# IF_RX.net
KiCad netlist of a schematic drawn in Altium Designer
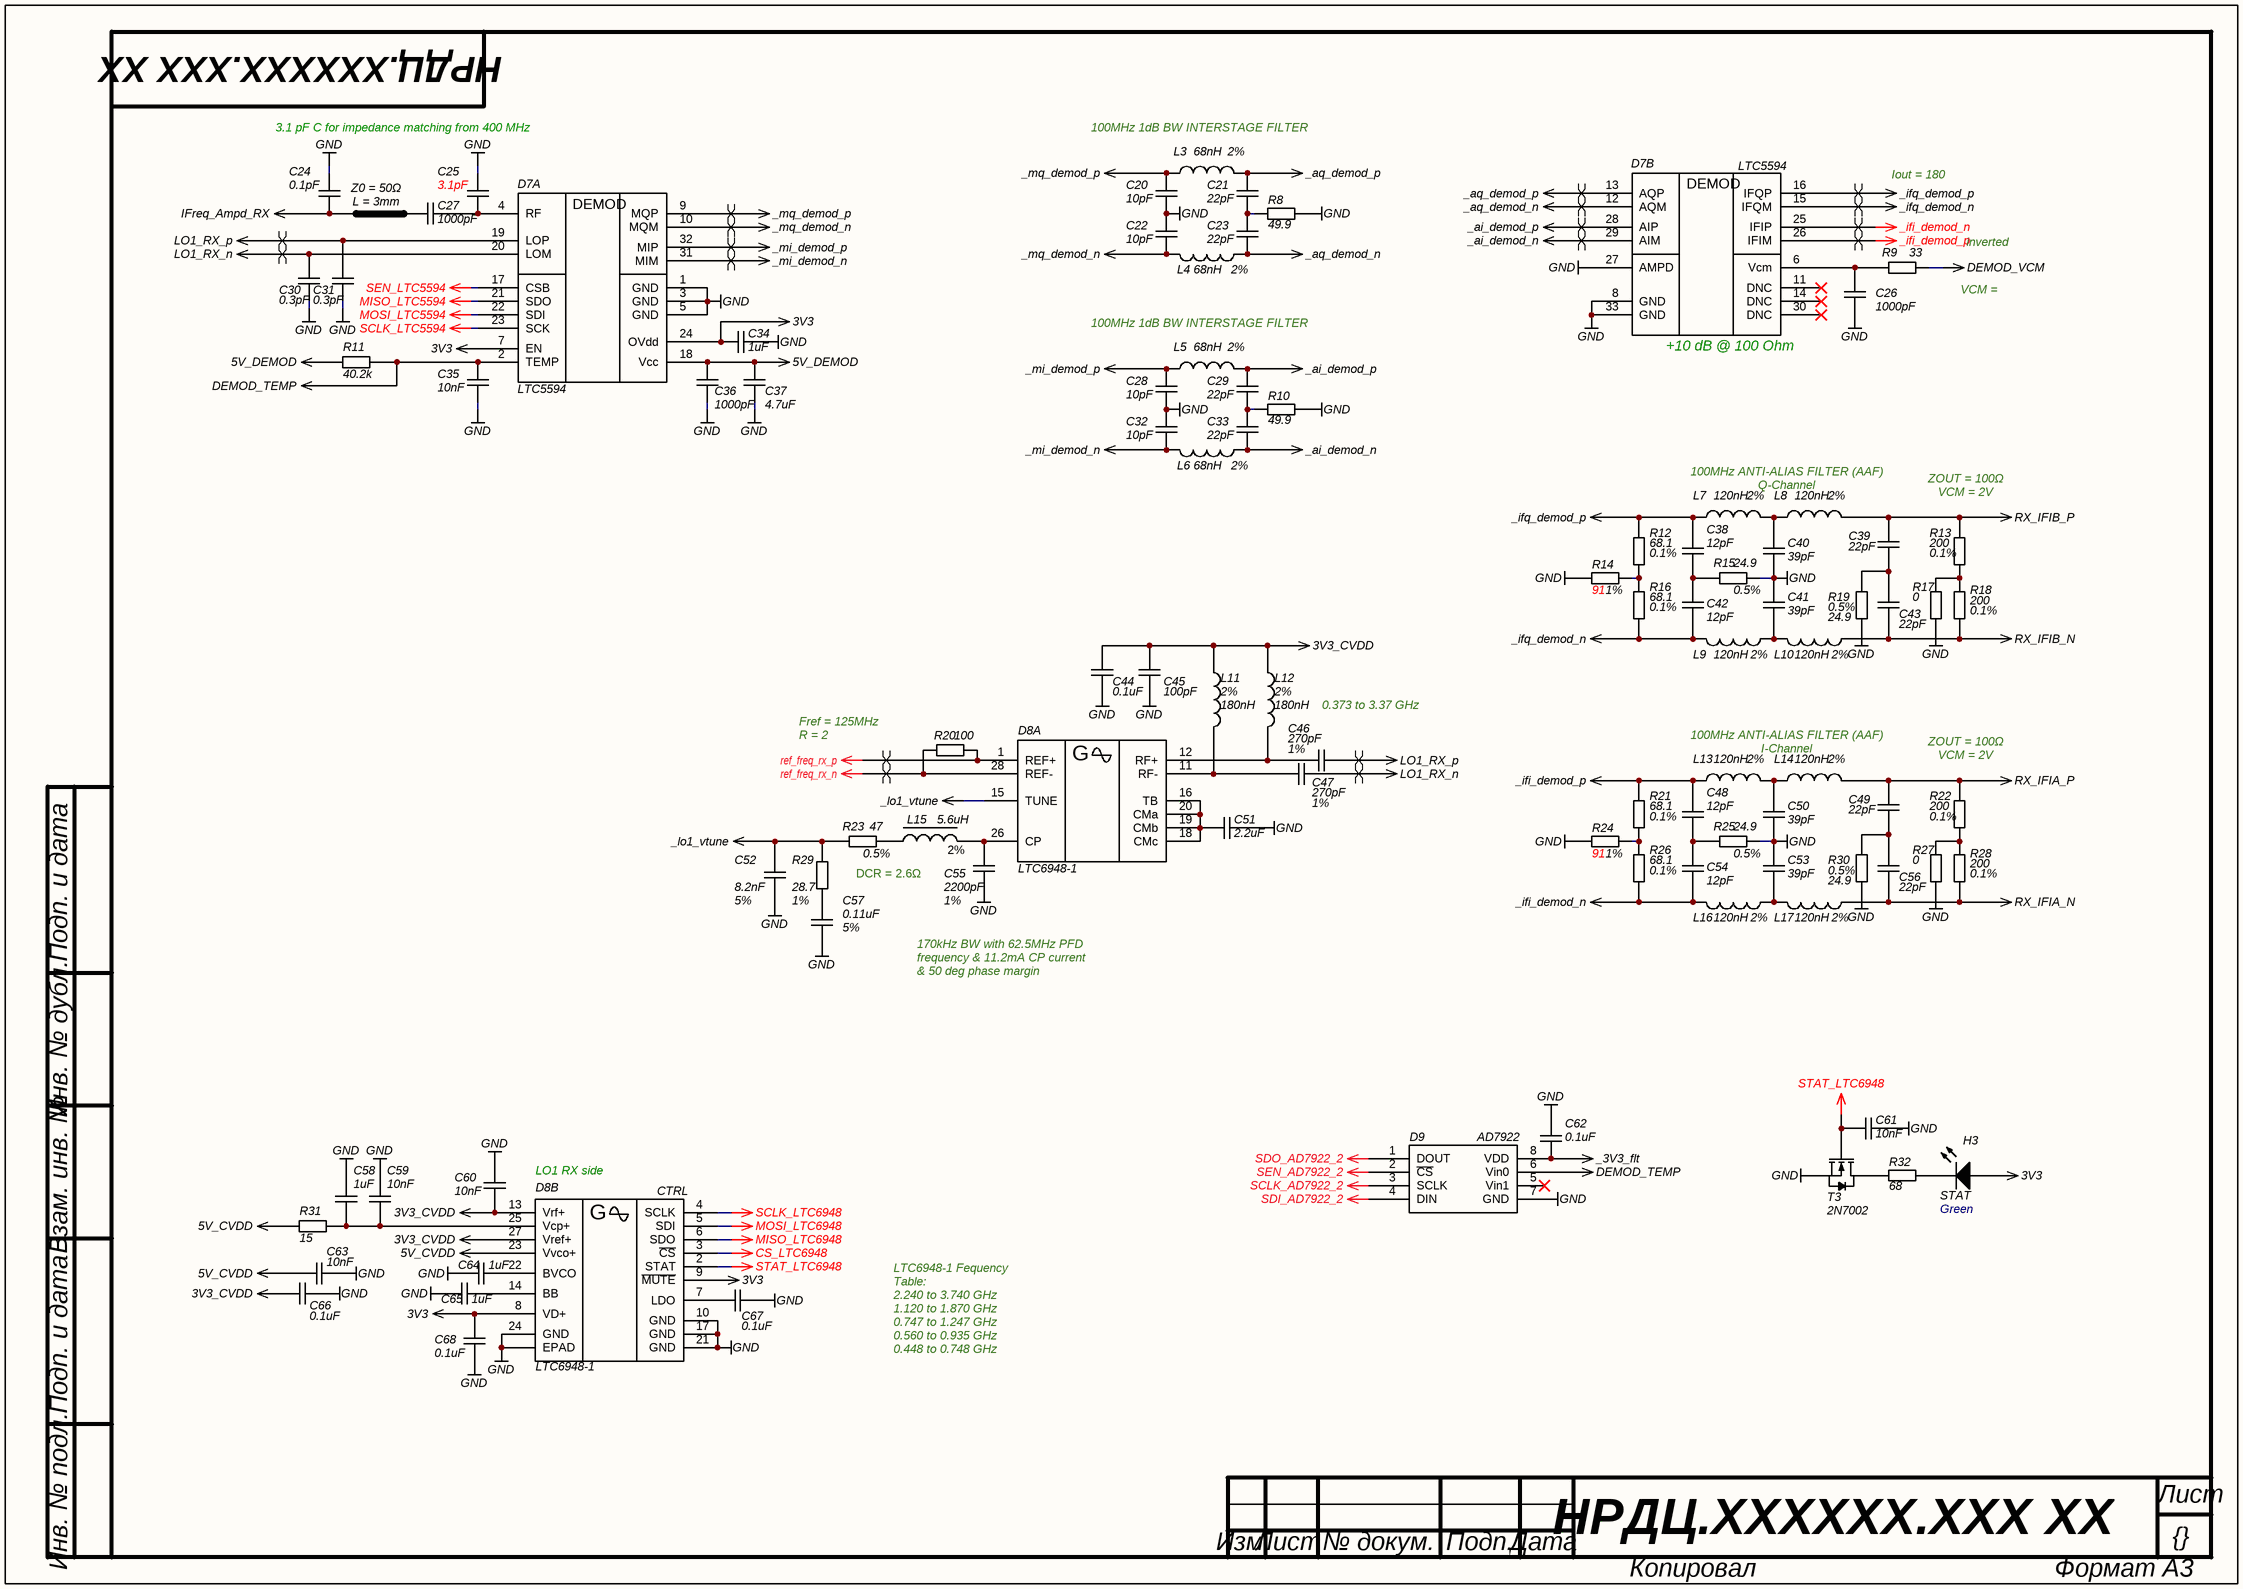
[diagram p0: IF_RX.SchDoc]

(export (version "E")
  (design (tool "Eeschema 10.0.6"))
  (components
    (comp (ref "C20")
      (value "10pF")
      (footprint "C0402")
      (description "SMD Capacitor")
      (fields (field (name "MANUFACTURER") "Murata") (field (name "TOLERANCE") "1%"))
      (libsource (lib "Kintex_SDR") (part "CAP"))
    )
    (comp (ref "C21")
      (value "22pF")
      (footprint "C0402")
      (description "SMD Capacitor")
      (fields (field (name "MANUFACTURER") "Murata") (field (name "TOLERANCE") "1%"))
      (libsource (lib "Kintex_SDR") (part "CAP"))
    )
    (comp (ref "C22")
      (value "10pF")
      (footprint "C0402")
      (description "SMD Capacitor")
      (fields (field (name "MANUFACTURER") "Murata") (field (name "TOLERANCE") "1%"))
      (libsource (lib "Kintex_SDR") (part "CAP"))
    )
    (comp (ref "C23")
      (value "22pF")
      (footprint "C0402")
      (description "SMD Capacitor")
      (fields (field (name "MANUFACTURER") "Murata") (field (name "TOLERANCE") "1%"))
      (libsource (lib "Kintex_SDR") (part "CAP"))
    )
    (comp (ref "C24")
      (value "0.1pF")
      (footprint "C0402")
      (description "SMD Capacitor")
      (fields (field (name "MANUFACTURER") "Murata") (field (name "TOLERANCE") "±0.05pF"))
      (libsource (lib "Kintex_SDR") (part "CAP"))
    )
    (comp (ref "C25")
      (value "3.1pF")
      (footprint "C0402")
      (description "SMD Capacitor")
      (fields (field (name "MANUFACTURER") "Murata") (field (name "TOLERANCE") "±0.05pF"))
      (libsource (lib "Kintex_SDR") (part "CAP"))
    )
    (comp (ref "C26")
      (value "1000pF")
      (footprint "C0402")
      (description "SMD Capacitor")
      (fields (field (name "MANUFACTURER") "Murata") (field (name "TOLERANCE") "5%"))
      (libsource (lib "Kintex_SDR") (part "CAP"))
    )
    (comp (ref "C27")
      (value "1000pF")
      (footprint "C0402")
      (description "SMD Capacitor")
      (fields (field (name "MANUFACTURER") "Murata") (field (name "TOLERANCE") "5%"))
      (libsource (lib "Kintex_SDR") (part "CAP"))
    )
    (comp (ref "C28")
      (value "10pF")
      (footprint "C0402")
      (description "SMD Capacitor")
      (fields (field (name "MANUFACTURER") "Murata") (field (name "TOLERANCE") "1%"))
      (libsource (lib "Kintex_SDR") (part "CAP"))
    )
    (comp (ref "C29")
      (value "22pF")
      (footprint "C0402")
      (description "SMD Capacitor")
      (fields (field (name "MANUFACTURER") "Murata") (field (name "TOLERANCE") "1%"))
      (libsource (lib "Kintex_SDR") (part "CAP"))
    )
    (comp (ref "C30")
      (value "0.3pF")
      (footprint "C0402")
      (description "SMD Capacitor")
      (fields (field (name "MANUFACTURER") "Murata") (field (name "TOLERANCE") "±0.05pF"))
      (libsource (lib "Kintex_SDR") (part "CAP"))
    )
    (comp (ref "C31")
      (value "0.3pF")
      (footprint "C0402")
      (description "SMD Capacitor")
      (fields (field (name "MANUFACTURER") "Murata") (field (name "TOLERANCE") "±0.05pF"))
      (libsource (lib "Kintex_SDR") (part "CAP"))
    )
    (comp (ref "C32")
      (value "10pF")
      (footprint "C0402")
      (description "SMD Capacitor")
      (fields (field (name "MANUFACTURER") "Murata") (field (name "TOLERANCE") "1%"))
      (libsource (lib "Kintex_SDR") (part "CAP"))
    )
    (comp (ref "C33")
      (value "22pF")
      (footprint "C0402")
      (description "SMD Capacitor")
      (fields (field (name "MANUFACTURER") "Murata") (field (name "TOLERANCE") "1%"))
      (libsource (lib "Kintex_SDR") (part "CAP"))
    )
    (comp (ref "C34")
      (value "1uF")
      (footprint "C0402")
      (description "SMD Capacitor")
      (fields (field (name "MANUFACTURER") "Murata") (field (name "TOLERANCE") "10%"))
      (libsource (lib "Kintex_SDR") (part "CAP"))
    )
    (comp (ref "C35")
      (value "10nF")
      (footprint "C0402")
      (description "SMD Capacitor")
      (fields (field (name "MANUFACTURER") "Murata") (field (name "TOLERANCE") "10%"))
      (libsource (lib "Kintex_SDR") (part "CAP"))
    )
    (comp (ref "C36")
      (value "1000pF")
      (footprint "C0402")
      (description "SMD Capacitor")
      (fields (field (name "MANUFACTURER") "Murata") (field (name "TOLERANCE") "5%"))
      (libsource (lib "Kintex_SDR") (part "CAP"))
    )
    (comp (ref "C37")
      (value "4.7uF")
      (footprint "C0805")
      (description "SMD Capacitor")
      (fields (field (name "MANUFACTURER") "Murata") (field (name "TOLERANCE") "10%"))
      (libsource (lib "Kintex_SDR") (part "CAP"))
    )
    (comp (ref "C38")
      (value "12pF")
      (footprint "C0402")
      (description "SMD Capacitor")
      (fields (field (name "MANUFACTURER") "Murata") (field (name "TOLERANCE") "1%"))
      (libsource (lib "Kintex_SDR") (part "CAP"))
    )
    (comp (ref "C39")
      (value "22pF")
      (footprint "C0402")
      (description "SMD Capacitor")
      (fields (field (name "MANUFACTURER") "Murata") (field (name "TOLERANCE") "1%"))
      (libsource (lib "Kintex_SDR") (part "CAP"))
    )
    (comp (ref "C40")
      (value "39pF")
      (footprint "C0402")
      (description "SMD Capacitor")
      (fields (field (name "MANUFACTURER") "Murata") (field (name "TOLERANCE") "1%"))
      (libsource (lib "Kintex_SDR") (part "CAP"))
    )
    (comp (ref "C41")
      (value "39pF")
      (footprint "C0402")
      (description "SMD Capacitor")
      (fields (field (name "MANUFACTURER") "Murata") (field (name "TOLERANCE") "1%"))
      (libsource (lib "Kintex_SDR") (part "CAP"))
    )
    (comp (ref "C42")
      (value "12pF")
      (footprint "C0402")
      (description "SMD Capacitor")
      (fields (field (name "MANUFACTURER") "Murata") (field (name "TOLERANCE") "1%"))
      (libsource (lib "Kintex_SDR") (part "CAP"))
    )
    (comp (ref "C43")
      (value "22pF")
      (footprint "C0402")
      (description "SMD Capacitor")
      (fields (field (name "MANUFACTURER") "Murata") (field (name "TOLERANCE") "1%"))
      (libsource (lib "Kintex_SDR") (part "CAP"))
    )
    (comp (ref "C44")
      (value "0.1uF")
      (footprint "C0402")
      (description "SMD Capacitor")
      (fields (field (name "MANUFACTURER") "Murata") (field (name "TOLERANCE") "10%"))
      (libsource (lib "Kintex_SDR") (part "CAP"))
    )
    (comp (ref "C45")
      (value "100pF")
      (footprint "C0402")
      (description "SMD Capacitor")
      (fields (field (name "MANUFACTURER") "Murata") (field (name "TOLERANCE") "1%"))
      (libsource (lib "Kintex_SDR") (part "CAP"))
    )
    (comp (ref "C46")
      (value "270pF")
      (footprint "C0402")
      (description "SMD Capacitor")
      (fields
        (field (name "MANUFACTURER") "Murata")
        (field (name "TOLERANCE") "1%")
        (field (name "VOLTAGE") "50V")
      )
      (libsource (lib "Kintex_SDR") (part "CAP"))
    )
    (comp (ref "C47")
      (value "270pF")
      (footprint "C0402")
      (description "SMD Capacitor")
      (fields
        (field (name "MANUFACTURER") "Murata")
        (field (name "TOLERANCE") "1%")
        (field (name "VOLTAGE") "50V")
      )
      (libsource (lib "Kintex_SDR") (part "CAP"))
    )
    (comp (ref "C48")
      (value "12pF")
      (footprint "C0402")
      (description "SMD Capacitor")
      (fields (field (name "MANUFACTURER") "Murata") (field (name "TOLERANCE") "1%"))
      (libsource (lib "Kintex_SDR") (part "CAP"))
    )
    (comp (ref "C49")
      (value "22pF")
      (footprint "C0402")
      (description "SMD Capacitor")
      (fields (field (name "MANUFACTURER") "Murata") (field (name "TOLERANCE") "1%"))
      (libsource (lib "Kintex_SDR") (part "CAP"))
    )
    (comp (ref "C50")
      (value "39pF")
      (footprint "C0402")
      (description "SMD Capacitor")
      (fields (field (name "MANUFACTURER") "Murata") (field (name "TOLERANCE") "1%"))
      (libsource (lib "Kintex_SDR") (part "CAP"))
    )
    (comp (ref "C51")
      (value "2.2uF")
      (footprint "C0603")
      (description "SMD Capacitor")
      (fields (field (name "MANUFACTURER") "Murata") (field (name "TOLERANCE") "10%"))
      (libsource (lib "Kintex_SDR") (part "CAP"))
    )
    (comp (ref "C52")
      (value "8.2nF")
      (footprint "C0603")
      (description "SMD Capacitor")
      (fields
        (field (name "MANUFACTURER") "Murata")
        (field (name "TOLERANCE") "5%")
        (field (name "VOLTAGE") "50V")
      )
      (libsource (lib "Kintex_SDR") (part "CAP"))
    )
    (comp (ref "C53")
      (value "39pF")
      (footprint "C0402")
      (description "SMD Capacitor")
      (fields (field (name "MANUFACTURER") "Murata") (field (name "TOLERANCE") "1%"))
      (libsource (lib "Kintex_SDR") (part "CAP"))
    )
    (comp (ref "C54")
      (value "12pF")
      (footprint "C0402")
      (description "SMD Capacitor")
      (fields (field (name "MANUFACTURER") "Murata") (field (name "TOLERANCE") "1%"))
      (libsource (lib "Kintex_SDR") (part "CAP"))
    )
    (comp (ref "C55")
      (value "2200pF")
      (footprint "C0603")
      (description "SMD Capacitor")
      (fields
        (field (name "MANUFACTURER") "Murata")
        (field (name "TOLERANCE") "1%")
        (field (name "VOLTAGE") "50V")
      )
      (libsource (lib "Kintex_SDR") (part "CAP"))
    )
    (comp (ref "C56")
      (value "22pF")
      (footprint "C0402")
      (description "SMD Capacitor")
      (fields (field (name "MANUFACTURER") "Murata") (field (name "TOLERANCE") "1%"))
      (libsource (lib "Kintex_SDR") (part "CAP"))
    )
    (comp (ref "C57")
      (value "0.11uF")
      (footprint "C0805")
      (description "SMD Capacitor")
      (fields
        (field (name "MANUFACTURER") "Murata")
        (field (name "TOLERANCE") "5%")
        (field (name "VOLTAGE") "50V")
      )
      (libsource (lib "Kintex_SDR") (part "CAP"))
    )
    (comp (ref "C58")
      (value "1uF")
      (footprint "C0402")
      (description "SMD Capacitor")
      (fields (field (name "MANUFACTURER") "Murata") (field (name "TOLERANCE") "10%"))
      (libsource (lib "Kintex_SDR") (part "CAP"))
    )
    (comp (ref "C59")
      (value "10nF")
      (footprint "C0402")
      (description "SMD Capacitor")
      (fields (field (name "MANUFACTURER") "Murata") (field (name "TOLERANCE") "10%"))
      (libsource (lib "Kintex_SDR") (part "CAP"))
    )
    (comp (ref "C60")
      (value "10nF")
      (footprint "C0402")
      (description "SMD Capacitor")
      (fields (field (name "MANUFACTURER") "Murata") (field (name "TOLERANCE") "10%"))
      (libsource (lib "Kintex_SDR") (part "CAP"))
    )
    (comp (ref "C61")
      (value "10nF")
      (footprint "C0402")
      (description "SMD Capacitor")
      (fields (field (name "MANUFACTURER") "Murata") (field (name "TOLERANCE") "10%"))
      (libsource (lib "Kintex_SDR") (part "CAP"))
    )
    (comp (ref "C62")
      (value "0.1uF")
      (footprint "C0402")
      (description "SMD Capacitor")
      (fields (field (name "MANUFACTURER") "Murata") (field (name "TOLERANCE") "10%"))
      (libsource (lib "Kintex_SDR") (part "CAP"))
    )
    (comp (ref "C63")
      (value "10nF")
      (footprint "C0402")
      (description "SMD Capacitor")
      (fields (field (name "MANUFACTURER") "Murata") (field (name "TOLERANCE") "10%"))
      (libsource (lib "Kintex_SDR") (part "CAP"))
    )
    (comp (ref "C64")
      (value "1uF")
      (footprint "C0402")
      (description "SMD Capacitor")
      (fields (field (name "MANUFACTURER") "Murata") (field (name "TOLERANCE") "10%"))
      (libsource (lib "Kintex_SDR") (part "CAP"))
    )
    (comp (ref "C65")
      (value "1uF")
      (footprint "C0402")
      (description "SMD Capacitor")
      (fields (field (name "MANUFACTURER") "Murata") (field (name "TOLERANCE") "10%"))
      (libsource (lib "Kintex_SDR") (part "CAP"))
    )
    (comp (ref "C66")
      (value "0.1uF")
      (footprint "C0402")
      (description "SMD Capacitor")
      (fields (field (name "MANUFACTURER") "Murata") (field (name "TOLERANCE") "10%"))
      (libsource (lib "Kintex_SDR") (part "CAP"))
    )
    (comp (ref "C67")
      (value "0.1uF")
      (footprint "C0402")
      (description "SMD Capacitor")
      (fields (field (name "MANUFACTURER") "Murata") (field (name "TOLERANCE") "10%"))
      (libsource (lib "Kintex_SDR") (part "CAP"))
    )
    (comp (ref "C68")
      (value "0.1uF")
      (footprint "C0402")
      (description "SMD Capacitor")
      (fields (field (name "MANUFACTURER") "Murata") (field (name "TOLERANCE") "10%"))
      (libsource (lib "Kintex_SDR") (part "CAP"))
    )
    (comp (ref "D7")
      (value "LTC5594")
      (footprint "DBLib:QFN-32")
      (description "Quadrature Demodulator")
      (fields (field (name "MANUFACTURER") "Analog Devices"))
      (libsource (lib "DBLib") (part "LTC5594"))
    )
    (comp (ref "D8")
      (value "LTC6948-1")
      (footprint "QFN-28")
      (description "The LTC®LTC6948 is a high performance, low noise, 6.39GHz  phase-locked loop (PLL)")
      (fields (field (name "MANUFACTURER") "Linear Technology") (field (name "VOLTAGE") "3.15 V ~ 5.25 V"))
      (libsource (lib "") (part "LTC6948_1"))
    )
    (comp (ref "D9")
      (value "AD7922")
      (footprint "MSOP-8")
      (description "1 MSPS, 10-/12-Bit ADC")
      (fields (field (name "MANUFACTURER") "Analog Device") (field (name "VOLTAGE") "2.35 V to 5.25 V"))
      (libsource (lib "Kintex_SDR") (part "AD79x2"))
    )
    (comp (ref "H3")
      (value "STAT")
      (footprint "LED_0805_Green")
      (description "CHIP LED LAMP")
      (fields (field (name "MANUFACTURER") "Kingbright") (field (name "COLOR") "Green"))
      (libsource (lib "DBLib") (part "LED"))
    )
    (comp (ref "L3")
      (value "68nH")
      (footprint "DBLib:L0402HPH")
      (description "Chip SMD Inductor")
      (fields
        (field (name "MANUFACTURER") "Coilcraft")
        (field (name "TOLERANCE") "2%")
        (field (name "Comment") "Inductor RF")
      )
      (libsource (lib "DBLib") (part "Inductor RF"))
    )
    (comp (ref "L4")
      (value "68nH")
      (footprint "DBLib:L0402HPH")
      (description "Chip SMD Inductor")
      (fields
        (field (name "MANUFACTURER") "Coilcraft")
        (field (name "TOLERANCE") "2%")
        (field (name "Comment") "Inductor RF")
      )
      (libsource (lib "") (part "Inductor RF_1"))
    )
    (comp (ref "L5")
      (value "68nH")
      (footprint "DBLib:L0402HPH")
      (description "Chip SMD Inductor")
      (fields
        (field (name "MANUFACTURER") "Coilcraft")
        (field (name "TOLERANCE") "2%")
        (field (name "Comment") "Inductor RF")
      )
      (libsource (lib "DBLib") (part "Inductor RF"))
    )
    (comp (ref "L6")
      (value "68nH")
      (footprint "DBLib:L0402HPH")
      (description "Chip SMD Inductor")
      (fields
        (field (name "MANUFACTURER") "Coilcraft")
        (field (name "TOLERANCE") "2%")
        (field (name "Comment") "Inductor RF")
      )
      (libsource (lib "") (part "Inductor RF_1"))
    )
    (comp (ref "L7")
      (value "120nH")
      (footprint "DBLib:L0402HPH")
      (description "Chip SMD Inductor")
      (fields
        (field (name "MANUFACTURER") "Coilcraft")
        (field (name "TOLERANCE") "2%")
        (field (name "Comment") "Inductor RF")
      )
      (libsource (lib "DBLib") (part "Inductor RF"))
    )
    (comp (ref "L8")
      (value "120nH")
      (footprint "DBLib:L0402HPH")
      (description "Chip SMD Inductor")
      (fields
        (field (name "MANUFACTURER") "Coilcraft")
        (field (name "TOLERANCE") "2%")
        (field (name "Comment") "Inductor RF")
      )
      (libsource (lib "DBLib") (part "Inductor RF"))
    )
    (comp (ref "L9")
      (value "120nH")
      (footprint "DBLib:L0402HPH")
      (description "Chip SMD Inductor")
      (fields
        (field (name "MANUFACTURER") "Coilcraft")
        (field (name "TOLERANCE") "2%")
        (field (name "Comment") "Inductor RF")
      )
      (libsource (lib "") (part "Inductor RF_1"))
    )
    (comp (ref "L10")
      (value "120nH")
      (footprint "DBLib:L0402HPH")
      (description "Chip SMD Inductor")
      (fields
        (field (name "MANUFACTURER") "Coilcraft")
        (field (name "TOLERANCE") "2%")
        (field (name "Comment") "Inductor RF")
      )
      (libsource (lib "") (part "Inductor RF_1"))
    )
    (comp (ref "L11")
      (value "180nH")
      (footprint "DBLib:L0603_HP")
      (description "Chip SMD Inductor")
      (fields
        (field (name "MANUFACTURER") "Coilcraft")
        (field (name "TOLERANCE") "2%")
        (field (name "Comment") "Inductor RF")
      )
      (libsource (lib "") (part "Inductor RF_1"))
    )
    (comp (ref "L12")
      (value "180nH")
      (footprint "DBLib:L0603_HP")
      (description "Chip SMD Inductor")
      (fields
        (field (name "MANUFACTURER") "Coilcraft")
        (field (name "TOLERANCE") "2%")
        (field (name "Comment") "Inductor RF")
      )
      (libsource (lib "") (part "Inductor RF_1"))
    )
    (comp (ref "L13")
      (value "120nH")
      (footprint "DBLib:L0402HPH")
      (description "Chip SMD Inductor")
      (fields
        (field (name "MANUFACTURER") "Coilcraft")
        (field (name "TOLERANCE") "2%")
        (field (name "Comment") "Inductor RF")
      )
      (libsource (lib "DBLib") (part "Inductor RF"))
    )
    (comp (ref "L14")
      (value "120nH")
      (footprint "DBLib:L0402HPH")
      (description "Chip SMD Inductor")
      (fields
        (field (name "MANUFACTURER") "Coilcraft")
        (field (name "TOLERANCE") "2%")
        (field (name "Comment") "Inductor RF")
      )
      (libsource (lib "DBLib") (part "Inductor RF"))
    )
    (comp (ref "L15")
      (value "5.6uH")
      (footprint "DBLib:L1008_LS")
      (description "Chip SMD Inductor")
      (fields
        (field (name "MANUFACTURER") "Coilcraft")
        (field (name "TOLERANCE") "2%")
        (field (name "Comment") "Inductor")
      )
      (libsource (lib "DBLib") (part "Inductor"))
    )
    (comp (ref "L16")
      (value "120nH")
      (footprint "DBLib:L0402HPH")
      (description "Chip SMD Inductor")
      (fields
        (field (name "MANUFACTURER") "Coilcraft")
        (field (name "TOLERANCE") "2%")
        (field (name "Comment") "Inductor RF")
      )
      (libsource (lib "") (part "Inductor RF_1"))
    )
    (comp (ref "L17")
      (value "120nH")
      (footprint "DBLib:L0402HPH")
      (description "Chip SMD Inductor")
      (fields
        (field (name "MANUFACTURER") "Coilcraft")
        (field (name "TOLERANCE") "2%")
        (field (name "Comment") "Inductor RF")
      )
      (libsource (lib "") (part "Inductor RF_1"))
    )
    (comp (ref "R8")
      (value "49.9")
      (footprint "R0402")
      (description "SMD Resistor")
      (fields (field (name "POWER") "0.063 Wt") (field (name "TOLERANCE") "0.5%"))
      (libsource (lib "Kintex_SDR") (part "RES"))
    )
    (comp (ref "R9")
      (value "33")
      (footprint "R0402")
      (description "SMD Resistor")
      (fields (field (name "POWER") "0.1 Wt") (field (name "TOLERANCE") "1%"))
      (libsource (lib "") (part "RES_1"))
    )
    (comp (ref "R10")
      (value "49.9")
      (footprint "R0402")
      (description "SMD Resistor")
      (fields (field (name "POWER") "0.063 Wt") (field (name "TOLERANCE") "0.5%"))
      (libsource (lib "Kintex_SDR") (part "RES"))
    )
    (comp (ref "R11")
      (value "40.2k")
      (footprint "R0402")
      (description "SMD Resistor")
      (fields (field (name "POWER") "0.063 Wt") (field (name "TOLERANCE") "1%"))
      (libsource (lib "Kintex_SDR") (part "RES"))
    )
    (comp (ref "R12")
      (value "68.1")
      (footprint "R0402")
      (description "SMD Resistor")
      (fields
        (field (name "POWER") "0.063 Wt")
        (field (name "TOLERANCE") "0.1%")
        (field (name "MANUFACTURER") "Panasonic Electronic Components")
      )
      (libsource (lib "") (part "RES_2"))
    )
    (comp (ref "R13")
      (value "200")
      (footprint "R0402")
      (description "SMD Resistor")
      (fields
        (field (name "POWER") "0.063 Wt")
        (field (name "TOLERANCE") "0.1%")
        (field (name "MANUFACTURER") "Panasonic Electronic Components")
      )
      (libsource (lib "") (part "RES_2"))
    )
    (comp (ref "R14")
      (value "91")
      (footprint "R0402")
      (description "SMD Resistor")
      (fields
        (field (name "POWER") "1/5 Wt")
        (field (name "TOLERANCE") "1%")
        (field (name "MANUFACTURER") "Panasonic Electronic Components")
      )
      (libsource (lib "Kintex_SDR") (part "RES"))
    )
    (comp (ref "R15")
      (value "24.9")
      (footprint "R0402")
      (description "SMD Resistor")
      (fields
        (field (name "POWER") "0.063 Wt")
        (field (name "TOLERANCE") "0.5%")
        (field (name "MANUFACTURER") "Panasonic Electronic Components")
      )
      (libsource (lib "Kintex_SDR") (part "RES"))
    )
    (comp (ref "R16")
      (value "68.1")
      (footprint "R0402")
      (description "SMD Resistor")
      (fields
        (field (name "POWER") "0.063 Wt")
        (field (name "TOLERANCE") "0.1%")
        (field (name "MANUFACTURER") "Panasonic Electronic Components")
      )
      (libsource (lib "") (part "RES_2"))
    )
    (comp (ref "R17")
      (value "0")
      (footprint "R0402")
      (description "SMD Resistor")
      (fields (field (name "POWER") "0.1 Wt") (field (name "TOLERANCE") "1%"))
      (libsource (lib "") (part "RES_2"))
    )
    (comp (ref "R18")
      (value "200")
      (footprint "R0402")
      (description "SMD Resistor")
      (fields
        (field (name "POWER") "0.063 Wt")
        (field (name "TOLERANCE") "0.1%")
        (field (name "MANUFACTURER") "Panasonic Electronic Components")
      )
      (libsource (lib "") (part "RES_2"))
    )
    (comp (ref "R19")
      (value "24.9")
      (footprint "R0402")
      (description "SMD Resistor")
      (fields
        (field (name "POWER") "0.063 Wt")
        (field (name "TOLERANCE") "0.5%")
        (field (name "MANUFACTURER") "Panasonic Electronic Components")
      )
      (libsource (lib "") (part "RES_2"))
    )
    (comp (ref "R20")
      (value "100")
      (footprint "R0402")
      (description "SMD Resistor")
      (fields (field (name "POWER") "0.062 Wt") (field (name "TOLERANCE") "5%"))
      (libsource (lib "Kintex_SDR") (part "RES"))
    )
    (comp (ref "R21")
      (value "68.1")
      (footprint "R0402")
      (description "SMD Resistor")
      (fields
        (field (name "POWER") "0.063 Wt")
        (field (name "TOLERANCE") "0.1%")
        (field (name "MANUFACTURER") "Panasonic Electronic Components")
      )
      (libsource (lib "") (part "RES_2"))
    )
    (comp (ref "R22")
      (value "200")
      (footprint "R0402")
      (description "SMD Resistor")
      (fields
        (field (name "POWER") "0.063 Wt")
        (field (name "TOLERANCE") "0.1%")
        (field (name "MANUFACTURER") "Panasonic Electronic Components")
      )
      (libsource (lib "") (part "RES_2"))
    )
    (comp (ref "R23")
      (value "47")
      (footprint "R0402")
      (description "SMD Resistor")
      (fields
        (field (name "POWER") "0.2 Wt")
        (field (name "TOLERANCE") "0.5%")
        (field (name "MANUFACTURER") "Panasonic Electronic Components")
      )
      (libsource (lib "") (part "RES_1"))
    )
    (comp (ref "R24")
      (value "91")
      (footprint "R0402")
      (description "SMD Resistor")
      (fields
        (field (name "POWER") "1/5 Wt")
        (field (name "TOLERANCE") "1%")
        (field (name "MANUFACTURER") "Panasonic Electronic Components")
      )
      (libsource (lib "Kintex_SDR") (part "RES"))
    )
    (comp (ref "R25")
      (value "24.9")
      (footprint "R0402")
      (description "SMD Resistor")
      (fields
        (field (name "POWER") "0.063 Wt")
        (field (name "TOLERANCE") "0.5%")
        (field (name "MANUFACTURER") "Panasonic Electronic Components")
      )
      (libsource (lib "Kintex_SDR") (part "RES"))
    )
    (comp (ref "R26")
      (value "68.1")
      (footprint "R0402")
      (description "SMD Resistor")
      (fields
        (field (name "POWER") "0.063 Wt")
        (field (name "TOLERANCE") "0.1%")
        (field (name "MANUFACTURER") "Panasonic Electronic Components")
      )
      (libsource (lib "") (part "RES_2"))
    )
    (comp (ref "R27")
      (value "0")
      (footprint "R0402")
      (description "SMD Resistor")
      (fields (field (name "POWER") "0.1 Wt") (field (name "TOLERANCE") "1%"))
      (libsource (lib "") (part "RES_2"))
    )
    (comp (ref "R28")
      (value "200")
      (footprint "R0402")
      (description "SMD Resistor")
      (fields
        (field (name "POWER") "0.063 Wt")
        (field (name "TOLERANCE") "0.1%")
        (field (name "MANUFACTURER") "Panasonic Electronic Components")
      )
      (libsource (lib "") (part "RES_2"))
    )
    (comp (ref "R29")
      (value "28.7")
      (footprint "R0402")
      (description "SMD Resistor")
      (fields
        (field (name "POWER") "0.2 Wt")
        (field (name "TOLERANCE") "1%")
        (field (name "MANUFACTURER") "Panasonic Electronic Components")
      )
      (libsource (lib "") (part "RES_2"))
    )
    (comp (ref "R30")
      (value "24.9")
      (footprint "R0402")
      (description "SMD Resistor")
      (fields
        (field (name "POWER") "0.063 Wt")
        (field (name "TOLERANCE") "0.5%")
        (field (name "MANUFACTURER") "Panasonic Electronic Components")
      )
      (libsource (lib "") (part "RES_2"))
    )
    (comp (ref "R31")
      (value "15")
      (footprint "R0603")
      (description "SMD Resistor")
      (fields (field (name "POWER") "0.1 Wt") (field (name "TOLERANCE") "1%"))
      (libsource (lib "") (part "RES_1"))
    )
    (comp (ref "R32")
      (value "68")
      (footprint "R0402")
      (description "SMD Resistor")
      (fields (field (name "POWER") "0.062 Wt") (field (name "TOLERANCE") "5%"))
      (libsource (lib "Kintex_SDR") (part "RES"))
    )
    (comp (ref "T3")
      (value "2N7002")
      (footprint "SOT-23")
      (description "N-Channel MOSFET 2N7002")
      (fields (field (name "VOLTAGE") "60V"))
      (libsource (lib "Kintex_SDR") (part "2N7002"))
    )
  )
  (nets
    (net (code "1") (name "3V3") (class "Default")
      (node (ref "C34") (pin "1") (pinfunction "1_1") (pintype "passive"))
      (node (ref "C68") (pin "2") (pinfunction "2_2") (pintype "passive"))
      (node (ref "D7") (pin "24") (pinfunction "OVdd_24") (pintype "passive"))
      (node (ref "D7") (pin "7") (pinfunction "EN_7") (pintype "passive"))
      (node (ref "D8") (pin "8") (pinfunction "VD+_8") (pintype "passive"))
      (node (ref "D8") (pin "9") (pinfunction "~{MUTE}_9") (pintype "passive"))
      (node (ref "H3") (pin "2") (pinfunction "A_2") (pintype "passive"))
    )
    (net (code "2") (name "3V3_CVDD") (class "Default")
      (node (ref "C44") (pin "2") (pinfunction "2_2") (pintype "passive"))
      (node (ref "C45") (pin "2") (pinfunction "2_2") (pintype "passive"))
      (node (ref "C60") (pin "2") (pinfunction "2_2") (pintype "passive"))
      (node (ref "C66") (pin "2") (pinfunction "2_2") (pintype "passive"))
      (node (ref "D8") (pin "13") (pinfunction "Vrf+_13") (pintype "passive"))
      (node (ref "D8") (pin "27") (pinfunction "Vref+_27") (pintype "passive"))
      (node (ref "L11") (pin "2") (pinfunction "2_2") (pintype "passive"))
      (node (ref "L12") (pin "2") (pinfunction "2_2") (pintype "passive"))
    )
    (net (code "3") (name "5V_CVDD") (class "Default")
      (node (ref "C63") (pin "1") (pinfunction "1_1") (pintype "passive"))
      (node (ref "D8") (pin "23") (pinfunction "Vvco+_23") (pintype "passive"))
      (node (ref "R31") (pin "2") (pinfunction "2_2") (pintype "passive"))
    )
    (net (code "4") (name "5V_DEMOD") (class "Default")
      (node (ref "C36") (pin "1") (pinfunction "1_1") (pintype "passive"))
      (node (ref "C37") (pin "2") (pinfunction "2_2") (pintype "passive"))
      (node (ref "D7") (pin "18") (pinfunction "Vcc_18") (pintype "passive"))
      (node (ref "R11") (pin "1") (pinfunction "1_1") (pintype "passive"))
    )
    (net (code "5") (name "CS_LTC6948") (class "Default")
      (node (ref "D8") (pin "3") (pinfunction "~{CS}_3") (pintype "passive"))
    )
    (net (code "6") (name "DEMOD_TEMP") (class "Default")
      (node (ref "C35") (pin "1") (pinfunction "1_1") (pintype "passive"))
      (node (ref "D7") (pin "2") (pinfunction "TEMP_2") (pintype "passive"))
      (node (ref "D9") (pin "6") (pinfunction "Vin0_6") (pintype "passive"))
      (node (ref "R11") (pin "2") (pinfunction "2_2") (pintype "passive"))
    )
    (net (code "7") (name "DEMOD_VCM") (class "Default")
      (node (ref "R9") (pin "1") (pinfunction "1_1") (pintype "passive"))
    )
    (net (code "8") (name "GND") (class "Default")
      (node (ref "C20") (pin "2") (pinfunction "2_2") (pintype "passive"))
      (node (ref "C22") (pin "1") (pinfunction "1_1") (pintype "passive"))
      (node (ref "C24") (pin "2") (pinfunction "2_2") (pintype "passive"))
      (node (ref "C25") (pin "2") (pinfunction "2_2") (pintype "passive"))
      (node (ref "C26") (pin "2") (pinfunction "2_2") (pintype "passive"))
      (node (ref "C28") (pin "2") (pinfunction "2_2") (pintype "passive"))
      (node (ref "C30") (pin "2") (pinfunction "2_2") (pintype "passive"))
      (node (ref "C31") (pin "2") (pinfunction "2_2") (pintype "passive"))
      (node (ref "C32") (pin "1") (pinfunction "1_1") (pintype "passive"))
      (node (ref "C34") (pin "2") (pinfunction "2_2") (pintype "passive"))
      (node (ref "C35") (pin "2") (pinfunction "2_2") (pintype "passive"))
      (node (ref "C36") (pin "2") (pinfunction "2_2") (pintype "passive"))
      (node (ref "C37") (pin "1") (pinfunction "1_1") (pintype "passive"))
      (node (ref "C40") (pin "2") (pinfunction "2_2") (pintype "passive"))
      (node (ref "C41") (pin "1") (pinfunction "1_1") (pintype "passive"))
      (node (ref "C44") (pin "1") (pinfunction "1_1") (pintype "passive"))
      (node (ref "C45") (pin "1") (pinfunction "1_1") (pintype "passive"))
      (node (ref "C50") (pin "2") (pinfunction "2_2") (pintype "passive"))
      (node (ref "C51") (pin "1") (pinfunction "1_1") (pintype "passive"))
      (node (ref "C52") (pin "1") (pinfunction "1_1") (pintype "passive"))
      (node (ref "C53") (pin "1") (pinfunction "1_1") (pintype "passive"))
      (node (ref "C55") (pin "1") (pinfunction "1_1") (pintype "passive"))
      (node (ref "C57") (pin "1") (pinfunction "1_1") (pintype "passive"))
      (node (ref "C58") (pin "1") (pinfunction "1_1") (pintype "passive"))
      (node (ref "C59") (pin "1") (pinfunction "1_1") (pintype "passive"))
      (node (ref "C60") (pin "1") (pinfunction "1_1") (pintype "passive"))
      (node (ref "C61") (pin "2") (pinfunction "2_2") (pintype "passive"))
      (node (ref "C62") (pin "2") (pinfunction "2_2") (pintype "passive"))
      (node (ref "C63") (pin "2") (pinfunction "2_2") (pintype "passive"))
      (node (ref "C64") (pin "1") (pinfunction "1_1") (pintype "passive"))
      (node (ref "C65") (pin "2") (pinfunction "2_2") (pintype "passive"))
      (node (ref "C66") (pin "1") (pinfunction "1_1") (pintype "passive"))
      (node (ref "C67") (pin "1") (pinfunction "1_1") (pintype "passive"))
      (node (ref "C68") (pin "1") (pinfunction "1_1") (pintype "passive"))
      (node (ref "D7") (pin "1") (pinfunction "GND_1") (pintype "passive"))
      (node (ref "D7") (pin "27") (pinfunction "AMPD_27") (pintype "passive"))
      (node (ref "D7") (pin "3") (pinfunction "GND_3") (pintype "passive"))
      (node (ref "D7") (pin "33") (pinfunction "GND_33") (pintype "passive"))
      (node (ref "D7") (pin "5") (pinfunction "GND_5") (pintype "passive"))
      (node (ref "D7") (pin "8") (pinfunction "GND_8") (pintype "passive"))
      (node (ref "D8") (pin "10") (pinfunction "GND_10") (pintype "passive"))
      (node (ref "D8") (pin "17") (pinfunction "GND_17") (pintype "passive"))
      (node (ref "D8") (pin "21") (pinfunction "GND_21") (pintype "passive"))
      (node (ref "D8") (pin "24") (pinfunction "GND_24") (pintype "passive"))
      (node (ref "D8") (pin "29") (pinfunction "EPAD_29") (pintype "passive"))
      (node (ref "D9") (pin "7") (pinfunction "GND_7") (pintype "passive"))
      (node (ref "R10") (pin "2") (pinfunction "2_2") (pintype "passive"))
      (node (ref "R14") (pin "1") (pinfunction "1_1") (pintype "passive"))
      (node (ref "R15") (pin "2") (pinfunction "2_2") (pintype "passive"))
      (node (ref "R17") (pin "2") (pinfunction "2_2") (pintype "passive"))
      (node (ref "R19") (pin "2") (pinfunction "2_2") (pintype "passive"))
      (node (ref "R24") (pin "1") (pinfunction "1_1") (pintype "passive"))
      (node (ref "R25") (pin "2") (pinfunction "2_2") (pintype "passive"))
      (node (ref "R27") (pin "2") (pinfunction "2_2") (pintype "passive"))
      (node (ref "R30") (pin "2") (pinfunction "2_2") (pintype "passive"))
      (node (ref "R8") (pin "2") (pinfunction "2_2") (pintype "passive"))
      (node (ref "T3") (pin "2") (pinfunction "S_2") (pintype "passive"))
    )
    (net (code "9") (name "IFreq_Ampd_RX") (class "Default")
      (node (ref "C24") (pin "1") (pinfunction "1_1") (pintype "passive"))
      (node (ref "C27") (pin "2") (pinfunction "2_2") (pintype "passive"))
    )
    (net (code "10") (name "LO1_RX_n") (class "Default")
      (node (ref "C30") (pin "1") (pinfunction "1_1") (pintype "passive"))
      (node (ref "C47") (pin "2") (pinfunction "2_2") (pintype "passive"))
      (node (ref "D7") (pin "20") (pinfunction "LOM_20") (pintype "passive"))
    )
    (net (code "11") (name "LO1_RX_p") (class "Default")
      (node (ref "C31") (pin "1") (pinfunction "1_1") (pintype "passive"))
      (node (ref "C46") (pin "2") (pinfunction "2_2") (pintype "passive"))
      (node (ref "D7") (pin "19") (pinfunction "LOP_19") (pintype "passive"))
    )
    (net (code "12") (name "MISO_LTC5594") (class "Default")
      (node (ref "D7") (pin "21") (pinfunction "SDO_21") (pintype "passive"))
    )
    (net (code "13") (name "MISO_LTC6948") (class "Default")
      (node (ref "D8") (pin "6") (pinfunction "SDO_6") (pintype "passive"))
    )
    (net (code "14") (name "MOSI_LTC5594") (class "Default")
      (node (ref "D7") (pin "22") (pinfunction "SDI_22") (pintype "passive"))
    )
    (net (code "15") (name "MOSI_LTC6948") (class "Default")
      (node (ref "D8") (pin "5") (pinfunction "SDI_5") (pintype "passive"))
    )
    (net (code "16") (name "Net-(C21-Pad2)") (class "Default")
      (node (ref "C21") (pin "2") (pinfunction "2_2") (pintype "passive"))
      (node (ref "C23") (pin "1") (pinfunction "1_1") (pintype "passive"))
      (node (ref "R8") (pin "1") (pinfunction "1_1") (pintype "passive"))
    )
    (net (code "17") (name "Net-(C29-Pad2)") (class "Default")
      (node (ref "C29") (pin "2") (pinfunction "2_2") (pintype "passive"))
      (node (ref "C33") (pin "1") (pinfunction "1_1") (pintype "passive"))
      (node (ref "R10") (pin "1") (pinfunction "1_1") (pintype "passive"))
    )
    (net (code "18") (name "Net-(C38-Pad2)") (class "Default")
      (node (ref "C38") (pin "2") (pinfunction "2_2") (pintype "passive"))
      (node (ref "C42") (pin "1") (pinfunction "1_1") (pintype "passive"))
      (node (ref "R15") (pin "1") (pinfunction "1_1") (pintype "passive"))
    )
    (net (code "19") (name "Net-(C39-Pad2)") (class "Default")
      (node (ref "C39") (pin "2") (pinfunction "2_2") (pintype "passive"))
      (node (ref "C43") (pin "1") (pinfunction "1_1") (pintype "passive"))
      (node (ref "R19") (pin "1") (pinfunction "1_1") (pintype "passive"))
    )
    (net (code "20") (name "Net-(C40-Pad1)") (class "Default")
      (node (ref "C40") (pin "1") (pinfunction "1_1") (pintype "passive"))
      (node (ref "L7") (pin "2") (pinfunction "2_2") (pintype "passive"))
      (node (ref "L8") (pin "1") (pinfunction "1_1") (pintype "passive"))
    )
    (net (code "21") (name "Net-(C41-Pad2)") (class "Default")
      (node (ref "C41") (pin "2") (pinfunction "2_2") (pintype "passive"))
      (node (ref "L10") (pin "1") (pinfunction "1_1") (pintype "passive"))
      (node (ref "L9") (pin "2") (pinfunction "2_2") (pintype "passive"))
    )
    (net (code "22") (name "Net-(C48-Pad2)") (class "Default")
      (node (ref "C48") (pin "2") (pinfunction "2_2") (pintype "passive"))
      (node (ref "C54") (pin "1") (pinfunction "1_1") (pintype "passive"))
      (node (ref "R25") (pin "1") (pinfunction "1_1") (pintype "passive"))
    )
    (net (code "23") (name "Net-(C49-Pad2)") (class "Default")
      (node (ref "C49") (pin "2") (pinfunction "2_2") (pintype "passive"))
      (node (ref "C56") (pin "1") (pinfunction "1_1") (pintype "passive"))
      (node (ref "R30") (pin "1") (pinfunction "1_1") (pintype "passive"))
    )
    (net (code "24") (name "Net-(C50-Pad1)") (class "Default")
      (node (ref "C50") (pin "1") (pinfunction "1_1") (pintype "passive"))
      (node (ref "L13") (pin "2") (pinfunction "2_2") (pintype "passive"))
      (node (ref "L14") (pin "1") (pinfunction "1_1") (pintype "passive"))
    )
    (net (code "25") (name "Net-(C53-Pad2)") (class "Default")
      (node (ref "C53") (pin "2") (pinfunction "2_2") (pintype "passive"))
      (node (ref "L16") (pin "2") (pinfunction "2_2") (pintype "passive"))
      (node (ref "L17") (pin "1") (pinfunction "1_1") (pintype "passive"))
    )
    (net (code "26") (name "Net-(C57-Pad2)") (class "Default")
      (node (ref "C57") (pin "2") (pinfunction "2_2") (pintype "passive"))
      (node (ref "R29") (pin "2") (pinfunction "2_2") (pintype "passive"))
    )
    (net (code "27") (name "Net-(D7A-RF)") (class "Default")
      (node (ref "C25") (pin "1") (pinfunction "1_1") (pintype "passive"))
      (node (ref "C27") (pin "1") (pinfunction "1_1") (pintype "passive"))
      (node (ref "D7") (pin "4") (pinfunction "RF_4") (pintype "passive"))
    )
    (net (code "28") (name "Net-(D7B-Vcm)") (class "Default")
      (node (ref "C26") (pin "1") (pinfunction "1_1") (pintype "passive"))
      (node (ref "D7") (pin "6") (pinfunction "Vcm_6") (pintype "passive"))
      (node (ref "R9") (pin "2") (pinfunction "2_2") (pintype "passive"))
    )
    (net (code "29") (name "Net-(D8A-CMa)") (class "Default")
      (node (ref "C51") (pin "2") (pinfunction "2_2") (pintype "passive"))
      (node (ref "D8") (pin "16") (pinfunction "TB_16") (pintype "passive"))
      (node (ref "D8") (pin "18") (pinfunction "CMc_18") (pintype "passive"))
      (node (ref "D8") (pin "19") (pinfunction "CMb_19") (pintype "passive"))
      (node (ref "D8") (pin "20") (pinfunction "CMa_20") (pintype "passive"))
    )
    (net (code "30") (name "Net-(D8A-CP)") (class "Default")
      (node (ref "C55") (pin "2") (pinfunction "2_2") (pintype "passive"))
      (node (ref "D8") (pin "26") (pinfunction "CP_26") (pintype "passive"))
      (node (ref "L15") (pin "2") (pinfunction "2_2") (pintype "passive"))
    )
    (net (code "31") (name "Net-(D8A-RF+)") (class "Default")
      (node (ref "C46") (pin "1") (pinfunction "1_1") (pintype "passive"))
      (node (ref "D8") (pin "12") (pinfunction "RF+_12") (pintype "passive"))
      (node (ref "L12") (pin "1") (pinfunction "1_1") (pintype "passive"))
    )
    (net (code "32") (name "Net-(D8A-RF-)") (class "Default")
      (node (ref "C47") (pin "1") (pinfunction "1_1") (pintype "passive"))
      (node (ref "D8") (pin "11") (pinfunction "RF-_11") (pintype "passive"))
      (node (ref "L11") (pin "1") (pinfunction "1_1") (pintype "passive"))
    )
    (net (code "33") (name "Net-(D8B-BB)") (class "Default")
      (node (ref "C65") (pin "1") (pinfunction "1_1") (pintype "passive"))
      (node (ref "D8") (pin "14") (pinfunction "BB_14") (pintype "passive"))
    )
    (net (code "34") (name "Net-(D8B-BVCO)") (class "Default")
      (node (ref "C64") (pin "2") (pinfunction "2_2") (pintype "passive"))
      (node (ref "D8") (pin "22") (pinfunction "BVCO_22") (pintype "passive"))
    )
    (net (code "35") (name "Net-(D8B-LDO)") (class "Default")
      (node (ref "C67") (pin "2") (pinfunction "2_2") (pintype "passive"))
      (node (ref "D8") (pin "7") (pinfunction "LDO_7") (pintype "passive"))
    )
    (net (code "36") (name "Net-(D8B-Vcp+)") (class "Default")
      (node (ref "C58") (pin "2") (pinfunction "2_2") (pintype "passive"))
      (node (ref "C59") (pin "2") (pinfunction "2_2") (pintype "passive"))
      (node (ref "D8") (pin "25") (pinfunction "Vcp+_25") (pintype "passive"))
      (node (ref "R31") (pin "1") (pinfunction "1_1") (pintype "passive"))
    )
    (net (code "37") (name "Net-(H3-K)") (class "Default")
      (node (ref "H3") (pin "1") (pinfunction "K_1") (pintype "passive"))
      (node (ref "R32") (pin "2") (pinfunction "2_2") (pintype "passive"))
    )
    (net (code "38") (name "Net-(L15-Pad1)") (class "Default")
      (node (ref "L15") (pin "1") (pinfunction "1_1") (pintype "passive"))
      (node (ref "R23") (pin "1") (pinfunction "1_1") (pintype "passive"))
    )
    (net (code "39") (name "Net-(R12-Pad2)") (class "Default")
      (node (ref "R12") (pin "2") (pinfunction "2_2") (pintype "passive"))
      (node (ref "R14") (pin "2") (pinfunction "2_2") (pintype "passive"))
      (node (ref "R16") (pin "1") (pinfunction "1_1") (pintype "passive"))
    )
    (net (code "40") (name "Net-(R13-Pad2)") (class "Default")
      (node (ref "R13") (pin "2") (pinfunction "2_2") (pintype "passive"))
      (node (ref "R17") (pin "1") (pinfunction "1_1") (pintype "passive"))
      (node (ref "R18") (pin "1") (pinfunction "1_1") (pintype "passive"))
    )
    (net (code "41") (name "Net-(R21-Pad2)") (class "Default")
      (node (ref "R21") (pin "2") (pinfunction "2_2") (pintype "passive"))
      (node (ref "R24") (pin "2") (pinfunction "2_2") (pintype "passive"))
      (node (ref "R26") (pin "1") (pinfunction "1_1") (pintype "passive"))
    )
    (net (code "42") (name "Net-(R22-Pad2)") (class "Default")
      (node (ref "R22") (pin "2") (pinfunction "2_2") (pintype "passive"))
      (node (ref "R27") (pin "1") (pinfunction "1_1") (pintype "passive"))
      (node (ref "R28") (pin "1") (pinfunction "1_1") (pintype "passive"))
    )
    (net (code "43") (name "Net-(T3-D)") (class "Default")
      (node (ref "R32") (pin "1") (pinfunction "1_1") (pintype "passive"))
      (node (ref "T3") (pin "3") (pinfunction "D_3") (pintype "passive"))
    )
    (net (code "44") (name "RX_IFIA_N") (class "Default")
      (node (ref "C56") (pin "2") (pinfunction "2_2") (pintype "passive"))
      (node (ref "L17") (pin "2") (pinfunction "2_2") (pintype "passive"))
      (node (ref "R28") (pin "2") (pinfunction "2_2") (pintype "passive"))
    )
    (net (code "45") (name "RX_IFIA_P") (class "Default")
      (node (ref "C49") (pin "1") (pinfunction "1_1") (pintype "passive"))
      (node (ref "L14") (pin "2") (pinfunction "2_2") (pintype "passive"))
      (node (ref "R22") (pin "1") (pinfunction "1_1") (pintype "passive"))
    )
    (net (code "46") (name "RX_IFIB_N") (class "Default")
      (node (ref "C43") (pin "2") (pinfunction "2_2") (pintype "passive"))
      (node (ref "L10") (pin "2") (pinfunction "2_2") (pintype "passive"))
      (node (ref "R18") (pin "2") (pinfunction "2_2") (pintype "passive"))
    )
    (net (code "47") (name "RX_IFIB_P") (class "Default")
      (node (ref "C39") (pin "1") (pinfunction "1_1") (pintype "passive"))
      (node (ref "L8") (pin "2") (pinfunction "2_2") (pintype "passive"))
      (node (ref "R13") (pin "1") (pinfunction "1_1") (pintype "passive"))
    )
    (net (code "48") (name "SCLK_AD7922_2") (class "Default")
      (node (ref "D9") (pin "3") (pinfunction "SCLK_3") (pintype "passive"))
    )
    (net (code "49") (name "SCLK_LTC5594") (class "Default")
      (node (ref "D7") (pin "23") (pinfunction "SCK_23") (pintype "passive"))
    )
    (net (code "50") (name "SCLK_LTC6948") (class "Default")
      (node (ref "D8") (pin "4") (pinfunction "SCLK_4") (pintype "passive"))
    )
    (net (code "51") (name "SDI_AD7922_2") (class "Default")
      (node (ref "D9") (pin "4") (pinfunction "DIN_4") (pintype "passive"))
    )
    (net (code "52") (name "SDO_AD7922_2") (class "Default")
      (node (ref "D9") (pin "1") (pinfunction "DOUT_1") (pintype "passive"))
    )
    (net (code "53") (name "SEN_AD7922_2") (class "Default")
      (node (ref "D9") (pin "2") (pinfunction "~{CS}_2") (pintype "passive"))
    )
    (net (code "54") (name "SEN_LTC5594") (class "Default")
      (node (ref "D7") (pin "17") (pinfunction "CSB_17") (pintype "passive"))
    )
    (net (code "55") (name "STAT_LTC6948") (class "Default")
      (node (ref "C61") (pin "1") (pinfunction "1_1") (pintype "passive"))
      (node (ref "D8") (pin "2") (pinfunction "STAT_2") (pintype "passive"))
      (node (ref "T3") (pin "1") (pinfunction "G_1") (pintype "passive"))
    )
    (net (code "56") (name "_3V3_flt") (class "Default")
      (node (ref "C62") (pin "1") (pinfunction "1_1") (pintype "passive"))
      (node (ref "D9") (pin "8") (pinfunction "VDD_8") (pintype "passive"))
    )
    (net (code "57") (name "_ai_demod_n") (class "Default")
      (node (ref "C33") (pin "2") (pinfunction "2_2") (pintype "passive"))
      (node (ref "D7") (pin "29") (pinfunction "AIM_29") (pintype "passive"))
      (node (ref "L6") (pin "2") (pinfunction "2_2") (pintype "passive"))
    )
    (net (code "58") (name "_ai_demod_p") (class "Default")
      (node (ref "C29") (pin "1") (pinfunction "1_1") (pintype "passive"))
      (node (ref "D7") (pin "28") (pinfunction "AIP_28") (pintype "passive"))
      (node (ref "L5") (pin "2") (pinfunction "2_2") (pintype "passive"))
    )
    (net (code "59") (name "_aq_demod_n") (class "Default")
      (node (ref "C23") (pin "2") (pinfunction "2_2") (pintype "passive"))
      (node (ref "D7") (pin "12") (pinfunction "AQM_12") (pintype "passive"))
      (node (ref "L4") (pin "2") (pinfunction "2_2") (pintype "passive"))
    )
    (net (code "60") (name "_aq_demod_p") (class "Default")
      (node (ref "C21") (pin "1") (pinfunction "1_1") (pintype "passive"))
      (node (ref "D7") (pin "13") (pinfunction "AQP_13") (pintype "passive"))
      (node (ref "L3") (pin "2") (pinfunction "2_2") (pintype "passive"))
    )
    (net (code "61") (name "_ifi_demod_n") (class "Default")
      (node (ref "C54") (pin "2") (pinfunction "2_2") (pintype "passive"))
      (node (ref "D7") (pin "25") (pinfunction "IFIP_25") (pintype "passive"))
      (node (ref "L16") (pin "1") (pinfunction "1_1") (pintype "passive"))
      (node (ref "R26") (pin "2") (pinfunction "2_2") (pintype "passive"))
    )
    (net (code "62") (name "_ifi_demod_p") (class "Default")
      (node (ref "C48") (pin "1") (pinfunction "1_1") (pintype "passive"))
      (node (ref "D7") (pin "26") (pinfunction "IFIM_26") (pintype "passive"))
      (node (ref "L13") (pin "1") (pinfunction "1_1") (pintype "passive"))
      (node (ref "R21") (pin "1") (pinfunction "1_1") (pintype "passive"))
    )
    (net (code "63") (name "_ifq_demod_n") (class "Default")
      (node (ref "C42") (pin "2") (pinfunction "2_2") (pintype "passive"))
      (node (ref "D7") (pin "15") (pinfunction "IFQM_15") (pintype "passive"))
      (node (ref "L9") (pin "1") (pinfunction "1_1") (pintype "passive"))
      (node (ref "R16") (pin "2") (pinfunction "2_2") (pintype "passive"))
    )
    (net (code "64") (name "_ifq_demod_p") (class "Default")
      (node (ref "C38") (pin "1") (pinfunction "1_1") (pintype "passive"))
      (node (ref "D7") (pin "16") (pinfunction "IFQP_16") (pintype "passive"))
      (node (ref "L7") (pin "1") (pinfunction "1_1") (pintype "passive"))
      (node (ref "R12") (pin "1") (pinfunction "1_1") (pintype "passive"))
    )
    (net (code "65") (name "_lo1_vtune") (class "Default")
      (node (ref "C52") (pin "2") (pinfunction "2_2") (pintype "passive"))
      (node (ref "D8") (pin "15") (pinfunction "TUNE_15") (pintype "passive"))
      (node (ref "R23") (pin "2") (pinfunction "2_2") (pintype "passive"))
      (node (ref "R29") (pin "1") (pinfunction "1_1") (pintype "passive"))
    )
    (net (code "66") (name "_mi_demod_n") (class "Default")
      (node (ref "C32") (pin "2") (pinfunction "2_2") (pintype "passive"))
      (node (ref "D7") (pin "31") (pinfunction "MIM_31") (pintype "passive"))
      (node (ref "L6") (pin "1") (pinfunction "1_1") (pintype "passive"))
    )
    (net (code "67") (name "_mi_demod_p") (class "Default")
      (node (ref "C28") (pin "1") (pinfunction "1_1") (pintype "passive"))
      (node (ref "D7") (pin "32") (pinfunction "MIP_32") (pintype "passive"))
      (node (ref "L5") (pin "1") (pinfunction "1_1") (pintype "passive"))
    )
    (net (code "68") (name "_mq_demod_n") (class "Default")
      (node (ref "C22") (pin "2") (pinfunction "2_2") (pintype "passive"))
      (node (ref "D7") (pin "10") (pinfunction "MQM_10") (pintype "passive"))
      (node (ref "L4") (pin "1") (pinfunction "1_1") (pintype "passive"))
    )
    (net (code "69") (name "_mq_demod_p") (class "Default")
      (node (ref "C20") (pin "1") (pinfunction "1_1") (pintype "passive"))
      (node (ref "D7") (pin "9") (pinfunction "MQP_9") (pintype "passive"))
      (node (ref "L3") (pin "1") (pinfunction "1_1") (pintype "passive"))
    )
    (net (code "70") (name "ref_freq_rx_n") (class "Default")
      (node (ref "D8") (pin "28") (pinfunction "REF-_28") (pintype "passive"))
      (node (ref "R20") (pin "1") (pinfunction "1_1") (pintype "passive"))
    )
    (net (code "71") (name "ref_freq_rx_p") (class "Default")
      (node (ref "D8") (pin "1") (pinfunction "REF+_1") (pintype "passive"))
      (node (ref "R20") (pin "2") (pinfunction "2_2") (pintype "passive"))
    )
    (net (code "72") (name "unconnected-(D7B-DNC-Pad11)") (class "Default")
      (node (ref "D7") (pin "11") (pinfunction "DNC_11") (pintype "passive+no_connect"))
    )
    (net (code "73") (name "unconnected-(D7B-DNC-Pad14)") (class "Default")
      (node (ref "D7") (pin "14") (pinfunction "DNC_14") (pintype "passive+no_connect"))
    )
    (net (code "74") (name "unconnected-(D7B-DNC-Pad30)") (class "Default")
      (node (ref "D7") (pin "30") (pinfunction "DNC_30") (pintype "passive+no_connect"))
    )
    (net (code "75") (name "unconnected-(D9-Vin1-Pad5)") (class "Default")
      (node (ref "D9") (pin "5") (pinfunction "Vin1_5") (pintype "passive+no_connect"))
    )
  )
)
